# probeStationBoardPcbWay.net
KiCad netlist of a schematic drawn in EAGLE
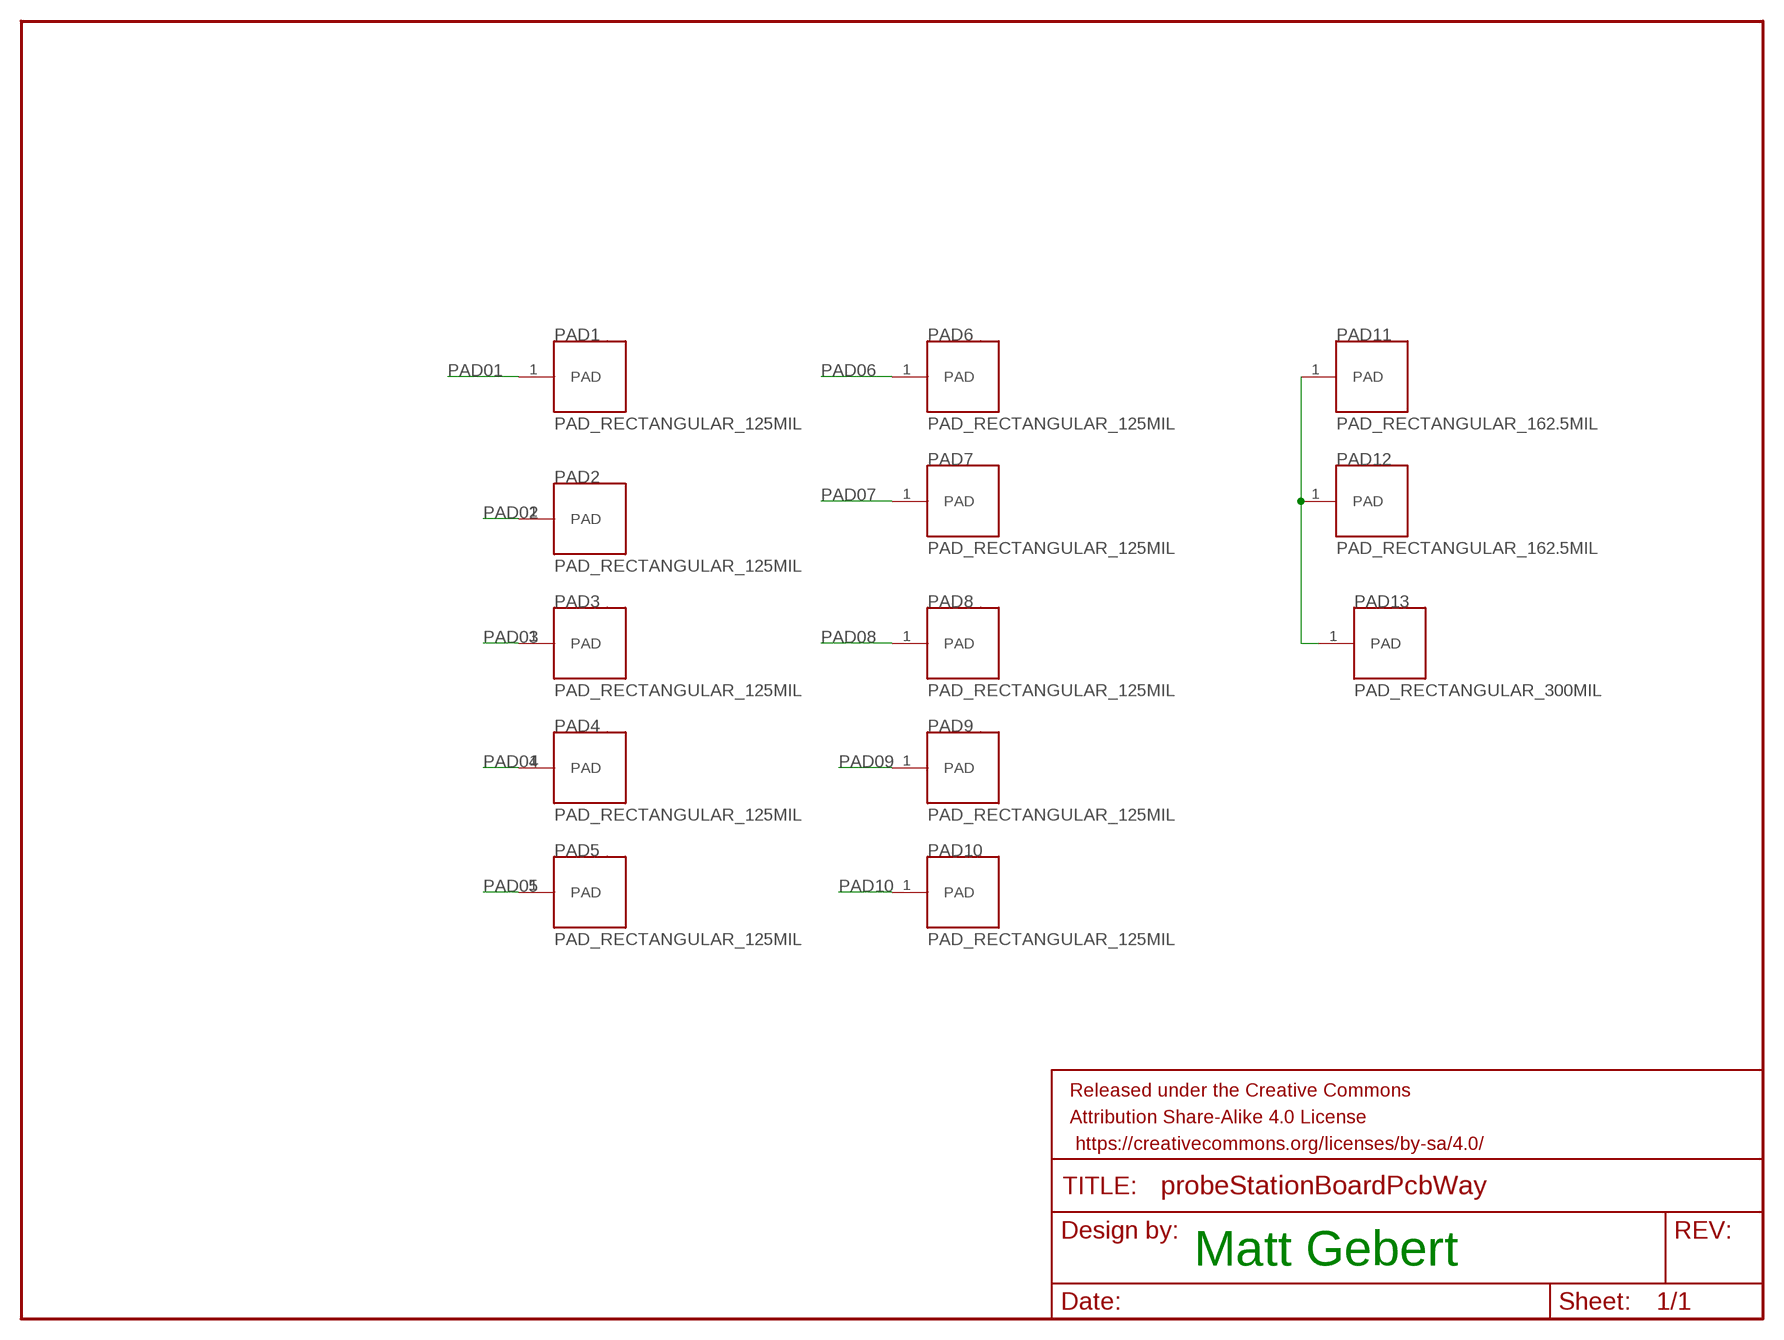
[diagram p0: schematic, sheet 1]

(export (version "E")
  (design (tool "Eeschema 10.0.6"))
  (components
    (comp (ref "FRAME1")
      (value "FRAME-LETTERNO_PACKAGE")
      (footprint "eagle-import:DUMMY")
      (fields (field (name "DESIGNER") "Nobody"))
      (libsource (lib "eagle-import") (part "FRAME-LETTERNO_PACKAGE"))
    )
    (comp (ref "PAD1")
      (value "PAD_RECTANGULAR_125MIL")
      (footprint "eagle-import:125MIL")
      (libsource (lib "eagle-import") (part "PAD_RECTANGULAR_125MIL"))
    )
    (comp (ref "PAD2")
      (value "PAD_RECTANGULAR_125MIL")
      (footprint "eagle-import:125MIL")
      (libsource (lib "eagle-import") (part "PAD_RECTANGULAR_125MIL"))
    )
    (comp (ref "PAD3")
      (value "PAD_RECTANGULAR_125MIL")
      (footprint "eagle-import:125MIL")
      (libsource (lib "eagle-import") (part "PAD_RECTANGULAR_125MIL"))
    )
    (comp (ref "PAD4")
      (value "PAD_RECTANGULAR_125MIL")
      (footprint "eagle-import:125MIL")
      (libsource (lib "eagle-import") (part "PAD_RECTANGULAR_125MIL"))
    )
    (comp (ref "PAD5")
      (value "PAD_RECTANGULAR_125MIL")
      (footprint "eagle-import:125MIL")
      (libsource (lib "eagle-import") (part "PAD_RECTANGULAR_125MIL"))
    )
    (comp (ref "PAD6")
      (value "PAD_RECTANGULAR_125MIL")
      (footprint "eagle-import:125MIL")
      (libsource (lib "eagle-import") (part "PAD_RECTANGULAR_125MIL"))
    )
    (comp (ref "PAD7")
      (value "PAD_RECTANGULAR_125MIL")
      (footprint "eagle-import:125MIL")
      (libsource (lib "eagle-import") (part "PAD_RECTANGULAR_125MIL"))
    )
    (comp (ref "PAD8")
      (value "PAD_RECTANGULAR_125MIL")
      (footprint "eagle-import:125MIL")
      (libsource (lib "eagle-import") (part "PAD_RECTANGULAR_125MIL"))
    )
    (comp (ref "PAD9")
      (value "PAD_RECTANGULAR_125MIL")
      (footprint "eagle-import:125MIL")
      (libsource (lib "eagle-import") (part "PAD_RECTANGULAR_125MIL"))
    )
    (comp (ref "PAD10")
      (value "PAD_RECTANGULAR_125MIL")
      (footprint "eagle-import:125MIL")
      (libsource (lib "eagle-import") (part "PAD_RECTANGULAR_125MIL"))
    )
    (comp (ref "PAD11")
      (value "PAD_RECTANGULAR_162.5MIL")
      (footprint "eagle-import:162.5MIL")
      (libsource (lib "eagle-import") (part "PAD_RECTANGULAR_162.5MIL"))
    )
    (comp (ref "PAD12")
      (value "PAD_RECTANGULAR_162.5MIL")
      (footprint "eagle-import:162.5MIL")
      (libsource (lib "eagle-import") (part "PAD_RECTANGULAR_162.5MIL"))
    )
    (comp (ref "PAD13")
      (value "PAD_RECTANGULAR_300MIL")
      (footprint "eagle-import:300MIL")
      (libsource (lib "eagle-import") (part "PAD_RECTANGULAR_300MIL"))
    )
  )
  (nets
    (net (code "1") (name "/PAD01") (class "Default")
      (node (ref "PAD1") (pin "1") (pinfunction "PAD_1") (pintype "bidirectional"))
    )
    (net (code "2") (name "/PAD02") (class "Default")
      (node (ref "PAD2") (pin "1") (pinfunction "PAD_1") (pintype "bidirectional"))
    )
    (net (code "3") (name "/PAD03") (class "Default")
      (node (ref "PAD3") (pin "1") (pinfunction "PAD_1") (pintype "bidirectional"))
    )
    (net (code "4") (name "/PAD04") (class "Default")
      (node (ref "PAD4") (pin "1") (pinfunction "PAD_1") (pintype "bidirectional"))
    )
    (net (code "5") (name "/PAD05") (class "Default")
      (node (ref "PAD5") (pin "1") (pinfunction "PAD_1") (pintype "bidirectional"))
    )
    (net (code "6") (name "/PAD06") (class "Default")
      (node (ref "PAD6") (pin "1") (pinfunction "PAD_1") (pintype "bidirectional"))
    )
    (net (code "7") (name "/PAD07") (class "Default")
      (node (ref "PAD7") (pin "1") (pinfunction "PAD_1") (pintype "bidirectional"))
    )
    (net (code "8") (name "/PAD08") (class "Default")
      (node (ref "PAD8") (pin "1") (pinfunction "PAD_1") (pintype "bidirectional"))
    )
    (net (code "9") (name "/PAD09") (class "Default")
      (node (ref "PAD9") (pin "1") (pinfunction "PAD_1") (pintype "bidirectional"))
    )
    (net (code "10") (name "/PAD10") (class "Default")
      (node (ref "PAD10") (pin "1") (pinfunction "PAD_1") (pintype "bidirectional"))
    )
    (net (code "11") (name "Net-(PAD11-PAD)") (class "Default")
      (node (ref "PAD11") (pin "1") (pinfunction "PAD_1") (pintype "bidirectional"))
      (node (ref "PAD12") (pin "1") (pinfunction "PAD_1") (pintype "bidirectional"))
      (node (ref "PAD13") (pin "1") (pinfunction "PAD_1") (pintype "bidirectional"))
    )
  )
)
